# SCH_Smart_led_driver_2022-09-08.net
KiCad netlist of a schematic drawn in EasyEDA
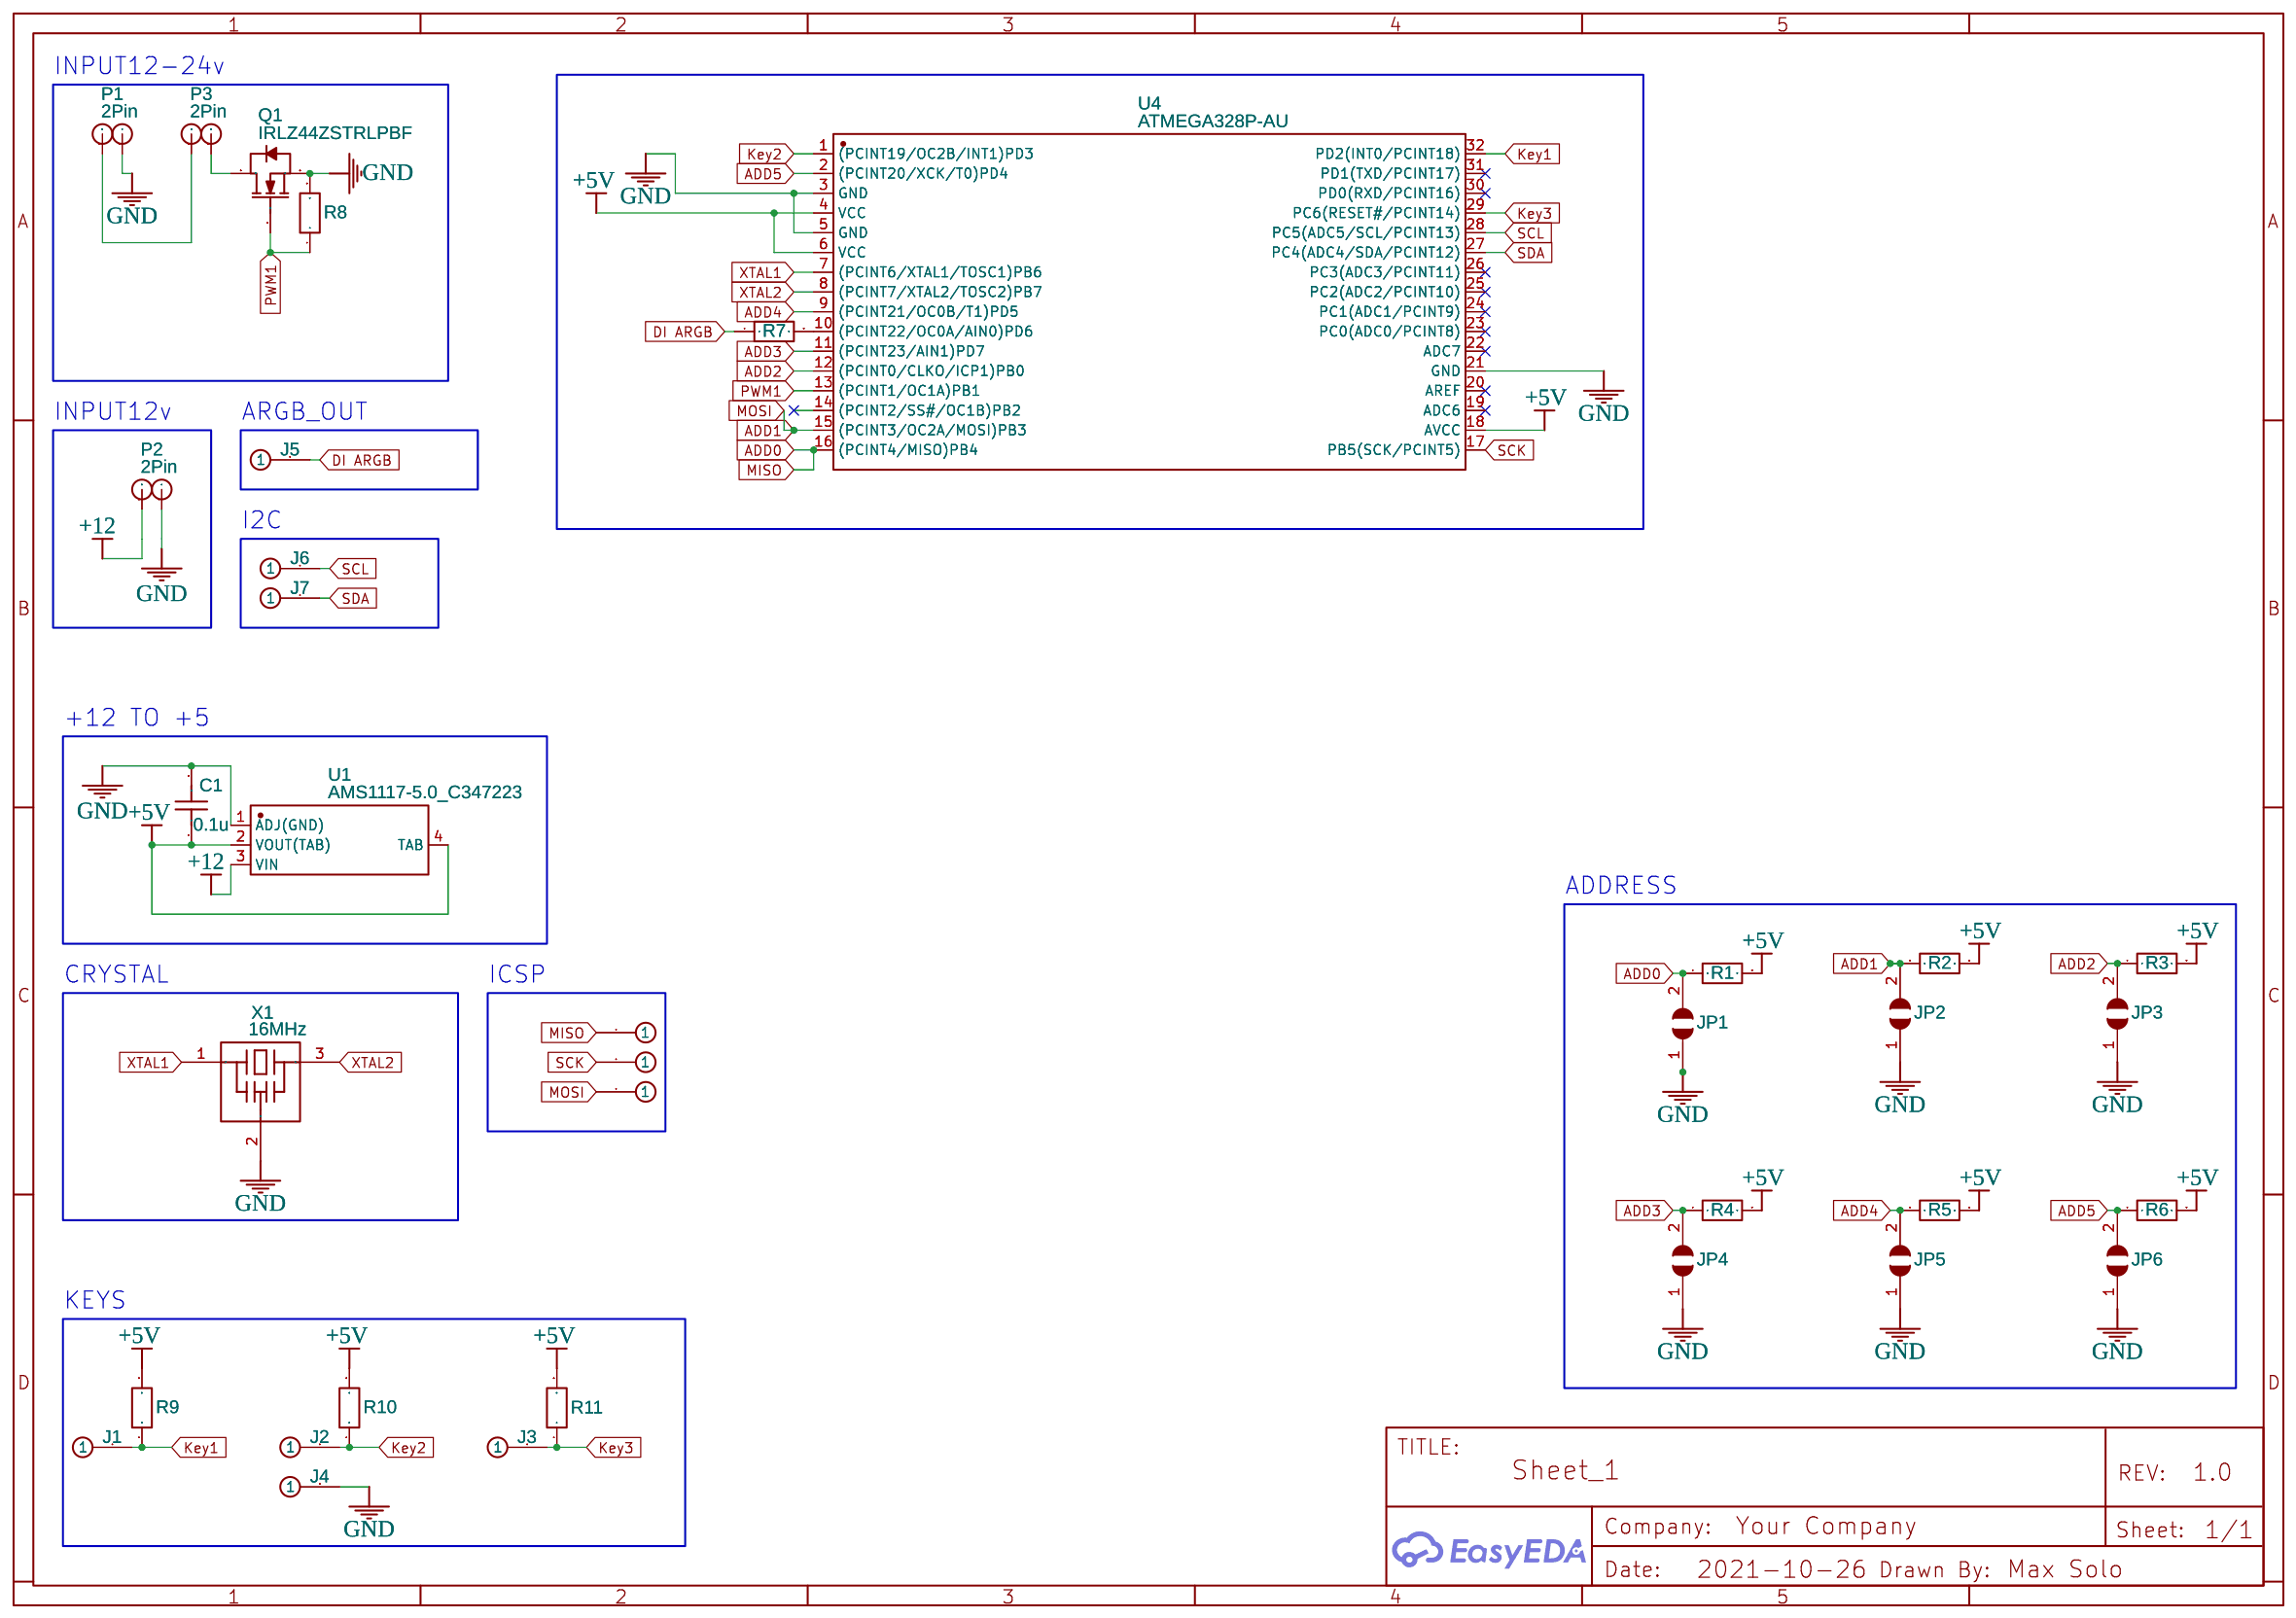
[diagram p0: schematic sheet]

(export (version "E")
  (design (tool "Eeschema 10.0.6"))
  (components
    (comp (ref "C1") (value "0.1u") (libsource (lib "") (part "C_0603_US")))
    (comp (ref "J1") (value "1PIN_SMD") (libsource (lib "") (part "1PIN_SMD")))
    (comp (ref "J2") (value "1PIN_SMD") (libsource (lib "") (part "1PIN_SMD")))
    (comp (ref "J3") (value "1PIN_SMD") (libsource (lib "") (part "1PIN_SMD")))
    (comp (ref "J4") (value "1PIN_SMD") (libsource (lib "") (part "1PIN_SMD")))
    (comp (ref "J5") (value "1PIN_SMD") (libsource (lib "") (part "1PIN_SMD")))
    (comp (ref "J6") (value "1PIN_SMD") (libsource (lib "") (part "1PIN_SMD")))
    (comp (ref "J7") (value "1PIN_SMD") (libsource (lib "") (part "1PIN_SMD")))
    (comp (ref "J8") (value "1PIN_SMD") (libsource (lib "") (part "1PIN_SMD_1")))
    (comp (ref "J9") (value "1PIN_SMD") (libsource (lib "") (part "1PIN_SMD_1")))
    (comp (ref "J12") (value "1PIN_SMD") (libsource (lib "") (part "1PIN_SMD_1")))
    (comp (ref "JP1")
      (value "MINI-ULTRA-LORAWAN-rescue_JUMPER-1-WAY-RocketScreamKicadLibrary")
      (libsource (lib "") (part "MINI-ULTRA-LORAWAN-rescue_JUMPER-1-WAY-RocketScreamKicadLibrary"))
    )
    (comp (ref "JP2")
      (value "MINI-ULTRA-LORAWAN-rescue_JUMPER-1-WAY-RocketScreamKicadLibrary")
      (libsource (lib "") (part "MINI-ULTRA-LORAWAN-rescue_JUMPER-1-WAY-RocketScreamKicadLibrary"))
    )
    (comp (ref "JP3")
      (value "MINI-ULTRA-LORAWAN-rescue_JUMPER-1-WAY-RocketScreamKicadLibrary")
      (libsource (lib "") (part "MINI-ULTRA-LORAWAN-rescue_JUMPER-1-WAY-RocketScreamKicadLibrary"))
    )
    (comp (ref "JP4")
      (value "MINI-ULTRA-LORAWAN-rescue_JUMPER-1-WAY-RocketScreamKicadLibrary")
      (libsource (lib "") (part "MINI-ULTRA-LORAWAN-rescue_JUMPER-1-WAY-RocketScreamKicadLibrary"))
    )
    (comp (ref "JP5")
      (value "MINI-ULTRA-LORAWAN-rescue_JUMPER-1-WAY-RocketScreamKicadLibrary")
      (libsource (lib "") (part "MINI-ULTRA-LORAWAN-rescue_JUMPER-1-WAY-RocketScreamKicadLibrary"))
    )
    (comp (ref "JP6")
      (value "MINI-ULTRA-LORAWAN-rescue_JUMPER-1-WAY-RocketScreamKicadLibrary")
      (libsource (lib "") (part "MINI-ULTRA-LORAWAN-rescue_JUMPER-1-WAY-RocketScreamKicadLibrary"))
    )
    (comp (ref "P1") (value "2Pin") (libsource (lib "") (part "2Pin")))
    (comp (ref "P2") (value "2Pin") (libsource (lib "") (part "2Pin")))
    (comp (ref "P3") (value "2Pin") (libsource (lib "") (part "2Pin")))
    (comp (ref "Q1")
      (value "IRLZ44ZSTRLPBF")
      (fields (field (name "BOM_Supplier Part") "C538201"))
      (libsource (lib "") (part "IRLZ44ZSTRLPBF"))
    )
    (comp (ref "R1") (value "10k") (libsource (lib "") (part "R_0603_EU_1")))
    (comp (ref "R2") (value "10k") (libsource (lib "") (part "R_0603_EU_1")))
    (comp (ref "R3") (value "10k") (libsource (lib "") (part "R_0603_EU_1")))
    (comp (ref "R4") (value "10k") (libsource (lib "") (part "R_0603_EU_1")))
    (comp (ref "R5") (value "10k") (libsource (lib "") (part "R_0603_EU_1")))
    (comp (ref "R6") (value "10k") (libsource (lib "") (part "R_0603_EU_1")))
    (comp (ref "R7") (value "300") (libsource (lib "") (part "R_0603_EU_1")))
    (comp (ref "R8") (value "10k") (libsource (lib "") (part "R_0603_EU")))
    (comp (ref "R9") (value "1k") (libsource (lib "") (part "R_0603_EU")))
    (comp (ref "R10") (value "1k") (libsource (lib "") (part "R_0603_EU")))
    (comp (ref "R11") (value "1k") (libsource (lib "") (part "R_0603_EU")))
    (comp (ref "U1")
      (value "AMS1117-5.0_C347223")
      (fields
        (field (name "BOM_Manufacturer Part") "AMS1117-5.0")
        (field (name "BOM_Supplier Part") "C347223")
      )
      (libsource (lib "") (part "AMS1117-5.0_C347223"))
    )
    (comp (ref "U4")
      (value "ATMEGA328P-AU")
      (fields (field (name "BOM_Supplier Part") "C14877"))
      (libsource (lib "") (part "ATMEGA328P-AU"))
    )
    (comp (ref "X1")
      (value "16MHz")
      (fields
        (field (name "BOM_Manufacturer Part") "CSTCE16M0V13C99-R0")
        (field (name "BOM_Supplier Part") "C118038")
      )
      (libsource (lib "") (part "CSTCE16M0V13C99-R0"))
    )
  )
  (nets
    (net (code "1") (name "+5V") (class "Default")
      (node (ref "C1") (pin "1") (pinfunction "1_1") (pintype "unspecified"))
      (node (ref "R1") (pin "2") (pinfunction "2_2") (pintype "unspecified"))
      (node (ref "R10") (pin "2") (pinfunction "2_2") (pintype "unspecified"))
      (node (ref "R11") (pin "2") (pinfunction "2_2") (pintype "unspecified"))
      (node (ref "R2") (pin "2") (pinfunction "2_2") (pintype "unspecified"))
      (node (ref "R3") (pin "2") (pinfunction "2_2") (pintype "unspecified"))
      (node (ref "R4") (pin "2") (pinfunction "2_2") (pintype "unspecified"))
      (node (ref "R5") (pin "2") (pinfunction "2_2") (pintype "unspecified"))
      (node (ref "R6") (pin "2") (pinfunction "2_2") (pintype "unspecified"))
      (node (ref "R9") (pin "2") (pinfunction "2_2") (pintype "unspecified"))
      (node (ref "U1") (pin "2") (pinfunction "VOUT(TAB)_2") (pintype "unspecified"))
      (node (ref "U1") (pin "4") (pinfunction "TAB_4") (pintype "unspecified"))
      (node (ref "U4") (pin "18") (pinfunction "AVCC_18") (pintype "unspecified"))
      (node (ref "U4") (pin "4") (pinfunction "VCC_4") (pintype "unspecified"))
      (node (ref "U4") (pin "6") (pinfunction "VCC_6") (pintype "unspecified"))
    )
    (net (code "2") (name "+12") (class "Default")
      (node (ref "P2") (pin "2") (pinfunction "2_2") (pintype "unspecified"))
      (node (ref "U1") (pin "3") (pinfunction "VIN_3") (pintype "unspecified"))
    )
    (net (code "3") (name "ADD0") (class "Default")
      (node (ref "J8") (pin "1") (pinfunction "1_1") (pintype "unspecified"))
      (node (ref "JP1") (pin "2") (pintype "unspecified"))
      (node (ref "R1") (pin "1") (pinfunction "1_1") (pintype "unspecified"))
      (node (ref "U4") (pin "16") (pinfunction "(PCINT4/MISO)PB4_16") (pintype "unspecified"))
    )
    (net (code "4") (name "ADD1") (class "Default")
      (node (ref "J12") (pin "1") (pinfunction "1_1") (pintype "unspecified"))
      (node (ref "JP2") (pin "2") (pintype "unspecified"))
      (node (ref "R2") (pin "1") (pinfunction "1_1") (pintype "unspecified"))
      (node (ref "U4") (pin "15") (pinfunction "(PCINT3/OC2A/MOSI)PB3_15") (pintype "unspecified"))
    )
    (net (code "5") (name "ADD2") (class "Default")
      (node (ref "JP3") (pin "2") (pintype "unspecified"))
      (node (ref "R3") (pin "1") (pinfunction "1_1") (pintype "unspecified"))
      (node (ref "U4") (pin "12") (pinfunction "(PCINT0/CLKO/ICP1)PB0_12") (pintype "unspecified"))
    )
    (net (code "6") (name "ADD3") (class "Default")
      (node (ref "JP4") (pin "2") (pintype "unspecified"))
      (node (ref "R4") (pin "1") (pinfunction "1_1") (pintype "unspecified"))
      (node (ref "U4") (pin "11") (pinfunction "(PCINT23/AIN1)PD7_11") (pintype "unspecified"))
    )
    (net (code "7") (name "ADD4") (class "Default")
      (node (ref "JP5") (pin "2") (pintype "unspecified"))
      (node (ref "R5") (pin "1") (pinfunction "1_1") (pintype "unspecified"))
      (node (ref "U4") (pin "9") (pinfunction "(PCINT21/OC0B/T1)PD5_9") (pintype "unspecified"))
    )
    (net (code "8") (name "ADD5") (class "Default")
      (node (ref "JP6") (pin "2") (pintype "unspecified"))
      (node (ref "R6") (pin "1") (pinfunction "1_1") (pintype "unspecified"))
      (node (ref "U4") (pin "2") (pinfunction "(PCINT20/XCK/T0)PD4_2") (pintype "unspecified"))
    )
    (net (code "9") (name "DI ARGB") (class "Default")
      (node (ref "J5") (pin "1") (pinfunction "1_1") (pintype "unspecified"))
      (node (ref "R7") (pin "1") (pinfunction "1_1") (pintype "unspecified"))
    )
    (net (code "10") (name "GND") (class "Default")
      (node (ref "C1") (pin "2") (pinfunction "2_2") (pintype "unspecified"))
      (node (ref "J4") (pin "1") (pinfunction "1_1") (pintype "unspecified"))
      (node (ref "JP1") (pin "1") (pintype "unspecified"))
      (node (ref "JP2") (pin "1") (pintype "unspecified"))
      (node (ref "JP3") (pin "1") (pintype "unspecified"))
      (node (ref "JP4") (pin "1") (pintype "unspecified"))
      (node (ref "JP5") (pin "1") (pintype "unspecified"))
      (node (ref "JP6") (pin "1") (pintype "unspecified"))
      (node (ref "P1") (pin "1") (pinfunction "1_1") (pintype "unspecified"))
      (node (ref "P2") (pin "1") (pinfunction "1_1") (pintype "unspecified"))
      (node (ref "Q1") (pin "3") (pinfunction "S_3") (pintype "unspecified"))
      (node (ref "R8") (pin "2") (pinfunction "2_2") (pintype "unspecified"))
      (node (ref "U1") (pin "1") (pinfunction "ADJ(GND)_1") (pintype "unspecified"))
      (node (ref "U4") (pin "21") (pinfunction "GND_21") (pintype "unspecified"))
      (node (ref "U4") (pin "3") (pinfunction "GND_3") (pintype "unspecified"))
      (node (ref "U4") (pin "5") (pinfunction "GND_5") (pintype "unspecified"))
      (node (ref "X1") (pin "2") (pinfunction "VSS_2") (pintype "passive"))
    )
    (net (code "11") (name "Key1") (class "Default")
      (node (ref "J1") (pin "1") (pinfunction "1_1") (pintype "unspecified"))
      (node (ref "R9") (pin "1") (pinfunction "1_1") (pintype "unspecified"))
      (node (ref "U4") (pin "32") (pinfunction "PD2(INT0/PCINT18)_32") (pintype "unspecified"))
    )
    (net (code "12") (name "Key2") (class "Default")
      (node (ref "J2") (pin "1") (pinfunction "1_1") (pintype "unspecified"))
      (node (ref "R10") (pin "1") (pinfunction "1_1") (pintype "unspecified"))
      (node (ref "U4") (pin "1") (pinfunction "(PCINT19/OC2B/INT1)PD3_1") (pintype "unspecified"))
    )
    (net (code "13") (name "Key3") (class "Default")
      (node (ref "J3") (pin "1") (pinfunction "1_1") (pintype "unspecified"))
      (node (ref "R11") (pin "1") (pinfunction "1_1") (pintype "unspecified"))
      (node (ref "U4") (pin "29") (pinfunction "PC6(RESET#/PCINT14)_29") (pintype "unspecified"))
    )
    (net (code "14") (name "Net-(P1-Pad2)") (class "Default")
      (node (ref "P1") (pin "2") (pinfunction "2_2") (pintype "unspecified"))
      (node (ref "P3") (pin "2") (pinfunction "2_2") (pintype "unspecified"))
    )
    (net (code "15") (name "Net-(Q1-D)") (class "Default")
      (node (ref "P3") (pin "1") (pinfunction "1_1") (pintype "unspecified"))
      (node (ref "Q1") (pin "2") (pinfunction "D_2") (pintype "unspecified"))
    )
    (net (code "16") (name "Net-(U4-(PCINT22{slash}OC0A{slash}AIN0)PD6)") (class "Default")
      (node (ref "R7") (pin "2") (pinfunction "2_2") (pintype "unspecified"))
      (node (ref "U4") (pin "10") (pinfunction "(PCINT22/OC0A/AIN0)PD6_10") (pintype "unspecified"))
    )
    (net (code "17") (name "PWM1") (class "Default")
      (node (ref "Q1") (pin "1") (pinfunction "G_1") (pintype "unspecified"))
      (node (ref "R8") (pin "1") (pinfunction "1_1") (pintype "unspecified"))
      (node (ref "U4") (pin "13") (pinfunction "(PCINT1/OC1A)PB1_13") (pintype "unspecified"))
    )
    (net (code "18") (name "SCK") (class "Default")
      (node (ref "J9") (pin "1") (pinfunction "1_1") (pintype "unspecified"))
      (node (ref "U4") (pin "17") (pinfunction "PB5(SCK/PCINT5)_17") (pintype "unspecified"))
    )
    (net (code "19") (name "SCL") (class "Default")
      (node (ref "J6") (pin "1") (pinfunction "1_1") (pintype "unspecified"))
      (node (ref "U4") (pin "28") (pinfunction "PC5(ADC5/SCL/PCINT13)_28") (pintype "unspecified"))
    )
    (net (code "20") (name "SDA") (class "Default")
      (node (ref "J7") (pin "1") (pinfunction "1_1") (pintype "unspecified"))
      (node (ref "U4") (pin "27") (pinfunction "PC4(ADC4/SDA/PCINT12)_27") (pintype "unspecified"))
    )
    (net (code "21") (name "XTAL1") (class "Default")
      (node (ref "U4") (pin "7") (pinfunction "(PCINT6/XTAL1/TOSC1)PB6_7") (pintype "unspecified"))
      (node (ref "X1") (pin "1") (pinfunction "1_1") (pintype "output"))
    )
    (net (code "22") (name "XTAL2") (class "Default")
      (node (ref "U4") (pin "8") (pinfunction "(PCINT7/XTAL2/TOSC2)PB7_8") (pintype "unspecified"))
      (node (ref "X1") (pin "3") (pinfunction "3_3") (pintype "input"))
    )
    (net (code "23") (name "unconnected-(U4-(PCINT2{slash}SS#{slash}OC1B)PB2-Pad14)") (class "Default")
      (node (ref "U4") (pin "14") (pinfunction "(PCINT2/SS#/OC1B)PB2_14") (pintype "unspecified+no_connect"))
    )
    (net (code "24") (name "unconnected-(U4-ADC6-Pad19)") (class "Default")
      (node (ref "U4") (pin "19") (pinfunction "ADC6_19") (pintype "unspecified+no_connect"))
    )
    (net (code "25") (name "unconnected-(U4-ADC7-Pad22)") (class "Default")
      (node (ref "U4") (pin "22") (pinfunction "ADC7_22") (pintype "unspecified+no_connect"))
    )
    (net (code "26") (name "unconnected-(U4-AREF-Pad20)") (class "Default")
      (node (ref "U4") (pin "20") (pinfunction "AREF_20") (pintype "unspecified+no_connect"))
    )
    (net (code "27") (name "unconnected-(U4-PC0(ADC0{slash}PCINT8)-Pad23)") (class "Default")
      (node (ref "U4") (pin "23") (pinfunction "PC0(ADC0/PCINT8)_23") (pintype "unspecified+no_connect"))
    )
    (net (code "28") (name "unconnected-(U4-PC1(ADC1{slash}PCINT9)-Pad24)") (class "Default")
      (node (ref "U4") (pin "24") (pinfunction "PC1(ADC1/PCINT9)_24") (pintype "unspecified+no_connect"))
    )
    (net (code "29") (name "unconnected-(U4-PC2(ADC2{slash}PCINT10)-Pad25)") (class "Default")
      (node (ref "U4") (pin "25") (pinfunction "PC2(ADC2/PCINT10)_25") (pintype "unspecified+no_connect"))
    )
    (net (code "30") (name "unconnected-(U4-PC3(ADC3{slash}PCINT11)-Pad26)") (class "Default")
      (node (ref "U4") (pin "26") (pinfunction "PC3(ADC3/PCINT11)_26") (pintype "unspecified+no_connect"))
    )
    (net (code "31") (name "unconnected-(U4-PD0(RXD{slash}PCINT16)-Pad30)") (class "Default")
      (node (ref "U4") (pin "30") (pinfunction "PD0(RXD/PCINT16)_30") (pintype "unspecified+no_connect"))
    )
    (net (code "32") (name "unconnected-(U4-PD1(TXD{slash}PCINT17)-Pad31)") (class "Default")
      (node (ref "U4") (pin "31") (pinfunction "PD1(TXD/PCINT17)_31") (pintype "unspecified+no_connect"))
    )
  )
)
